# mainboard_rs485_v1_3.net
KiCad netlist of a schematic drawn in Altium Designer
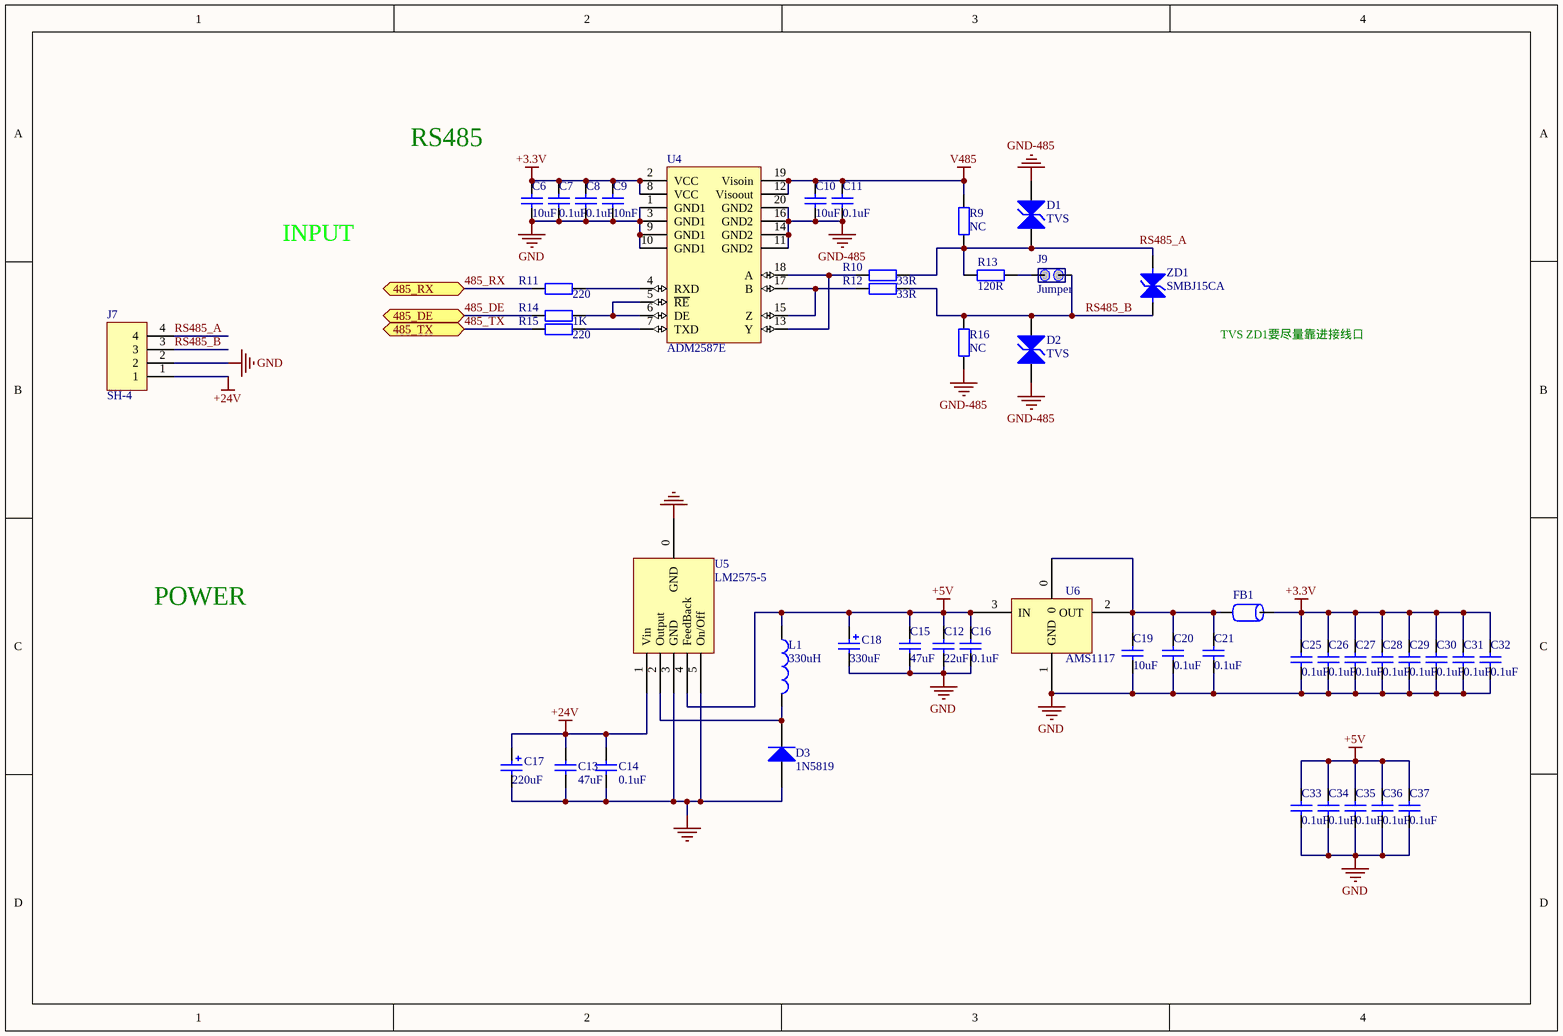
[diagram p0: mainboard_rs485.v1.3.SchDoc]

(export (version "E")
  (design (tool "Eeschema 10.0.6"))
  (components
    (comp (ref "C6")
      (value "10uF")
      (footprint "0805")
      (description "Capacitor")
      (fields (field (name "PUBLISHER") "Altium Limited"))
      (libsource (lib "TIAN's Schlib") (part "Cap"))
    )
    (comp (ref "C7")
      (value "0.1uF")
      (footprint "0805")
      (description "Capacitor")
      (fields (field (name "PUBLISHER") "Altium Limited"))
      (libsource (lib "TIAN's Schlib") (part "Cap"))
    )
    (comp (ref "C8")
      (value "0.1uF")
      (footprint "0805")
      (description "Capacitor")
      (fields (field (name "PUBLISHER") "Altium Limited"))
      (libsource (lib "TIAN's Schlib") (part "Cap"))
    )
    (comp (ref "C9")
      (value "10nF")
      (footprint "0805")
      (description "Capacitor")
      (fields (field (name "PUBLISHER") "Altium Limited"))
      (libsource (lib "TIAN's Schlib") (part "Cap"))
    )
    (comp (ref "C10")
      (value "10uF")
      (footprint "0805")
      (description "Capacitor")
      (fields (field (name "PUBLISHER") "Altium Limited"))
      (libsource (lib "TIAN's Schlib") (part "Cap"))
    )
    (comp (ref "C11")
      (value "0.1uF")
      (footprint "0805")
      (description "Capacitor")
      (fields (field (name "PUBLISHER") "Altium Limited"))
      (libsource (lib "TIAN's Schlib") (part "Cap"))
    )
    (comp (ref "C12") (value "22uF") (footprint "1206") (libsource (lib "Componet") (part "Cap0805")))
    (comp (ref "C13")
      (value "47uF")
      (footprint "1812")
      (description "Capacitor")
      (fields (field (name "PUBLISHER") "Altium Limited"))
      (libsource (lib "Miscellaneous Devices") (part "Cap"))
    )
    (comp (ref "C14")
      (value "0.1uF")
      (footprint "0805")
      (description "Capacitor")
      (fields (field (name "PUBLISHER") "Altium Limited"))
      (libsource (lib "Miscellaneous Devices") (part "Cap"))
    )
    (comp (ref "C15") (value "47uF") (footprint "1812") (libsource (lib "Componet") (part "Cap0805")))
    (comp (ref "C16") (value "0.1uF") (footprint "0805") (libsource (lib "Componet") (part "Cap0805")))
    (comp (ref "C17")
      (value "220uF")
      (footprint "CAP-5mm")
      (description "Polarized Capacitor (Radial)")
      (fields (field (name "PUBLISHER") "Altium Limited"))
      (libsource (lib "Miscellaneous Devices") (part "Cap Pol1"))
    )
    (comp (ref "C18")
      (value "330uF")
      (footprint "CAP-5mm")
      (description "Polarized Capacitor (Radial)")
      (fields (field (name "PUBLISHER") "Altium Limited"))
      (libsource (lib "Miscellaneous Devices") (part "Cap Pol1"))
    )
    (comp (ref "C19") (value "10uF") (footprint "0805") (libsource (lib "Componet") (part "Cap0805")))
    (comp (ref "C20") (value "0.1uF") (footprint "0805") (libsource (lib "Componet") (part "Cap0805")))
    (comp (ref "C21") (value "0.1uF") (footprint "0805") (libsource (lib "Componet") (part "Cap0805")))
    (comp (ref "C25") (value "0.1uF") (footprint "0805") (libsource (lib "Componet") (part "Cap0805")))
    (comp (ref "C26") (value "0.1uF") (footprint "0805") (libsource (lib "Componet") (part "Cap0805")))
    (comp (ref "C27") (value "0.1uF") (footprint "0805") (libsource (lib "Componet") (part "Cap0805")))
    (comp (ref "C28") (value "0.1uF") (footprint "0805") (libsource (lib "Componet") (part "Cap0805")))
    (comp (ref "C29") (value "0.1uF") (footprint "0805") (libsource (lib "Componet") (part "Cap0805")))
    (comp (ref "C30") (value "0.1uF") (footprint "0805") (libsource (lib "Componet") (part "Cap0805")))
    (comp (ref "C31") (value "0.1uF") (footprint "0805") (libsource (lib "Componet") (part "Cap0805")))
    (comp (ref "C32") (value "0.1uF") (footprint "0805") (libsource (lib "Componet") (part "Cap0805")))
    (comp (ref "C33") (value "0.1uF") (footprint "0805") (libsource (lib "Componet") (part "Cap0805")))
    (comp (ref "C34") (value "0.1uF") (footprint "0805") (libsource (lib "Componet") (part "Cap0805")))
    (comp (ref "C35") (value "0.1uF") (footprint "0805") (libsource (lib "Componet") (part "Cap0805")))
    (comp (ref "C36") (value "0.1uF") (footprint "0805") (libsource (lib "Componet") (part "Cap0805")))
    (comp (ref "C37") (value "0.1uF") (footprint "0805") (libsource (lib "Componet") (part "Cap0805")))
    (comp (ref "D1")
      (value "TVS")
      (footprint "SMBJ_DO-214")
      (fields (field (name "PUBLISHER") "Altium Limited"))
      (libsource (lib "TIAN's Schlib") (part "TVS"))
    )
    (comp (ref "D2")
      (value "TVS")
      (footprint "SMBJ_DO-214")
      (fields (field (name "PUBLISHER") "Altium Limited"))
      (libsource (lib "TIAN's Schlib") (part "TVS"))
    )
    (comp (ref "D3")
      (value "1N5819")
      (footprint "Diode_TP2")
      (description "High Conductance Fast Diode")
      (fields (field (name "PUBLISHER") "Altium Limited"))
      (libsource (lib "Miscellaneous Devices") (part "Diode 1N4148"))
    )
    (comp (ref "FB1") (value "FERRITE") (footprint "0805") (libsource (lib "Connector") (part "FERRITE")))
    (comp (ref "J7") (value "SH-4") (footprint "PWR") (libsource (lib "Connector") (part "SH-4")))
    (comp (ref "J9") (value "Jumper") (footprint "J254-2") (libsource (lib "Connector") (part "Jumper")))
    (comp (ref "L1")
      (value "330uH")
      (footprint "Inductance")
      (description "Inductor")
      (fields (field (name "PUBLISHER") "Altium Limited"))
      (libsource (lib "Miscellaneous Devices") (part "Inductor"))
    )
    (comp (ref "R9")
      (value "NC")
      (footprint "0805")
      (description "Resistor")
      (fields (field (name "PUBLISHER") "Altium Limited"))
      (libsource (lib "") (part "Res2_1"))
    )
    (comp (ref "R10")
      (value "33R")
      (footprint "0805")
      (description "Resistor")
      (fields (field (name "PUBLISHER") "Altium Limited"))
      (libsource (lib "TIAN's Schlib") (part "Res2"))
    )
    (comp (ref "R11")
      (value "220")
      (footprint "0805")
      (description "Resistor")
      (fields (field (name "PUBLISHER") "Altium Limited"))
      (libsource (lib "") (part "Res2_1"))
    )
    (comp (ref "R12")
      (value "33R")
      (footprint "0805")
      (description "Resistor")
      (fields (field (name "PUBLISHER") "Altium Limited"))
      (libsource (lib "TIAN's Schlib") (part "Res2"))
    )
    (comp (ref "R13")
      (value "120R")
      (footprint "0805")
      (description "Resistor")
      (fields (field (name "PUBLISHER") "Altium Limited"))
      (libsource (lib "") (part "Res2_2"))
    )
    (comp (ref "R14")
      (value "1K")
      (footprint "0805")
      (description "Resistor")
      (fields (field (name "PUBLISHER") "Altium Limited"))
      (libsource (lib "") (part "Res2_1"))
    )
    (comp (ref "R15")
      (value "220")
      (footprint "0805")
      (description "Resistor")
      (fields (field (name "PUBLISHER") "Altium Limited"))
      (libsource (lib "") (part "Res2_1"))
    )
    (comp (ref "R16")
      (value "NC")
      (footprint "0805")
      (description "Resistor")
      (fields (field (name "PUBLISHER") "Altium Limited"))
      (libsource (lib "") (part "Res2_1"))
    )
    (comp (ref "U4")
      (value "ADM2587E")
      (footprint "SOIC_W_20")
      (description "isolated DC-DC RS485")
      (libsource (lib "TIAN's Schlib") (part "ADM2587E"))
    )
    (comp (ref "U5") (value "LM2575-5") (footprint "TO-263") (libsource (lib "Leon") (part "LM25XX")))
    (comp (ref "U6") (value "AMS1117") (footprint "TO-223") (libsource (lib "Chip") (part "AMS1117")))
    (comp (ref "ZD1")
      (value "SMBJ15CA")
      (footprint "DO-214AA/SMB")
      (description "瞬态抑制二极管")
      (libsource (lib "ALARM") (part "TVS"))
    )
  )
  (nets
    (net (code "1") (name "+3.3V") (class "Default")
      (node (ref "C25") (pin "2") (pinfunction "2_2") (pintype "passive"))
      (node (ref "C26") (pin "2") (pinfunction "2_2") (pintype "passive"))
      (node (ref "C27") (pin "2") (pinfunction "2_2") (pintype "passive"))
      (node (ref "C28") (pin "2") (pinfunction "2_2") (pintype "passive"))
      (node (ref "C29") (pin "2") (pinfunction "2_2") (pintype "passive"))
      (node (ref "C30") (pin "2") (pinfunction "2_2") (pintype "passive"))
      (node (ref "C31") (pin "2") (pinfunction "2_2") (pintype "passive"))
      (node (ref "C32") (pin "2") (pinfunction "2_2") (pintype "passive"))
      (node (ref "C6") (pin "2") (pinfunction "2_2") (pintype "passive"))
      (node (ref "C7") (pin "2") (pinfunction "2_2") (pintype "passive"))
      (node (ref "C8") (pin "2") (pinfunction "2_2") (pintype "passive"))
      (node (ref "C9") (pin "2") (pinfunction "2_2") (pintype "passive"))
      (node (ref "FB1") (pin "2") (pinfunction "2_2") (pintype "passive"))
      (node (ref "U4") (pin "2") (pinfunction "VCC_2") (pintype "passive"))
      (node (ref "U4") (pin "8") (pinfunction "VCC_8") (pintype "passive"))
    )
    (net (code "2") (name "+5V") (class "Default")
      (node (ref "C12") (pin "2") (pinfunction "2_2") (pintype "passive"))
      (node (ref "C15") (pin "2") (pinfunction "2_2") (pintype "passive"))
      (node (ref "C16") (pin "2") (pinfunction "2_2") (pintype "passive"))
      (node (ref "C18") (pin "1") (pinfunction "1_1") (pintype "passive"))
      (node (ref "C33") (pin "2") (pinfunction "2_2") (pintype "passive"))
      (node (ref "C34") (pin "2") (pinfunction "2_2") (pintype "passive"))
      (node (ref "C35") (pin "2") (pinfunction "2_2") (pintype "passive"))
      (node (ref "C36") (pin "2") (pinfunction "2_2") (pintype "passive"))
      (node (ref "C37") (pin "2") (pinfunction "2_2") (pintype "passive"))
      (node (ref "L1") (pin "1") (pinfunction "1_1") (pintype "passive"))
      (node (ref "U5") (pin "4") (pinfunction "FeedBack_4") (pintype "passive"))
      (node (ref "U6") (pin "3") (pinfunction "IN_3") (pintype "passive"))
    )
    (net (code "3") (name "+24V") (class "Default")
      (node (ref "C13") (pin "2") (pinfunction "2_2") (pintype "passive"))
      (node (ref "C14") (pin "2") (pinfunction "2_2") (pintype "passive"))
      (node (ref "C17") (pin "1") (pinfunction "1_1") (pintype "passive"))
      (node (ref "J7") (pin "1") (pinfunction "1_1") (pintype "passive"))
      (node (ref "U5") (pin "1") (pinfunction "Vin_1") (pintype "passive"))
    )
    (net (code "4") (name "/485_DE") (class "Default")
      (node (ref "R14") (pin "1") (pinfunction "1_1") (pintype "passive"))
    )
    (net (code "5") (name "/485_RX") (class "Default")
      (node (ref "R11") (pin "1") (pinfunction "1_1") (pintype "passive"))
    )
    (net (code "6") (name "/485_TX") (class "Default")
      (node (ref "R15") (pin "1") (pinfunction "1_1") (pintype "passive"))
    )
    (net (code "7") (name "/RS485_A") (class "Default")
      (node (ref "D1") (pin "2") (pinfunction "K_2") (pintype "passive"))
      (node (ref "J7") (pin "4") (pinfunction "4_4") (pintype "passive"))
      (node (ref "R10") (pin "2") (pinfunction "2_2") (pintype "passive"))
      (node (ref "R13") (pin "2") (pinfunction "2_2") (pintype "passive"))
      (node (ref "R9") (pin "1") (pinfunction "1_1") (pintype "passive"))
      (node (ref "ZD1") (pin "1") (pinfunction "1_1") (pintype "passive"))
    )
    (net (code "8") (name "/RS485_B") (class "Default")
      (node (ref "D2") (pin "2") (pinfunction "K_2") (pintype "passive"))
      (node (ref "J7") (pin "3") (pinfunction "3_3") (pintype "passive"))
      (node (ref "J9") (pin "1") (pinfunction "1_1") (pintype "passive"))
      (node (ref "R12") (pin "2") (pinfunction "2_2") (pintype "passive"))
      (node (ref "R16") (pin "2") (pinfunction "2_2") (pintype "passive"))
      (node (ref "ZD1") (pin "2") (pinfunction "2_2") (pintype "passive"))
    )
    (net (code "9") (name "GND") (class "Default")
      (node (ref "C12") (pin "1") (pinfunction "1_1") (pintype "passive"))
      (node (ref "C13") (pin "1") (pinfunction "1_1") (pintype "passive"))
      (node (ref "C14") (pin "1") (pinfunction "1_1") (pintype "passive"))
      (node (ref "C15") (pin "1") (pinfunction "1_1") (pintype "passive"))
      (node (ref "C16") (pin "1") (pinfunction "1_1") (pintype "passive"))
      (node (ref "C17") (pin "2") (pinfunction "2_2") (pintype "passive"))
      (node (ref "C18") (pin "2") (pinfunction "2_2") (pintype "passive"))
      (node (ref "C19") (pin "1") (pinfunction "1_1") (pintype "passive"))
      (node (ref "C20") (pin "1") (pinfunction "1_1") (pintype "passive"))
      (node (ref "C21") (pin "1") (pinfunction "1_1") (pintype "passive"))
      (node (ref "C25") (pin "1") (pinfunction "1_1") (pintype "passive"))
      (node (ref "C26") (pin "1") (pinfunction "1_1") (pintype "passive"))
      (node (ref "C27") (pin "1") (pinfunction "1_1") (pintype "passive"))
      (node (ref "C28") (pin "1") (pinfunction "1_1") (pintype "passive"))
      (node (ref "C29") (pin "1") (pinfunction "1_1") (pintype "passive"))
      (node (ref "C30") (pin "1") (pinfunction "1_1") (pintype "passive"))
      (node (ref "C31") (pin "1") (pinfunction "1_1") (pintype "passive"))
      (node (ref "C32") (pin "1") (pinfunction "1_1") (pintype "passive"))
      (node (ref "C33") (pin "1") (pinfunction "1_1") (pintype "passive"))
      (node (ref "C34") (pin "1") (pinfunction "1_1") (pintype "passive"))
      (node (ref "C35") (pin "1") (pinfunction "1_1") (pintype "passive"))
      (node (ref "C36") (pin "1") (pinfunction "1_1") (pintype "passive"))
      (node (ref "C37") (pin "1") (pinfunction "1_1") (pintype "passive"))
      (node (ref "C6") (pin "1") (pinfunction "1_1") (pintype "passive"))
      (node (ref "C7") (pin "1") (pinfunction "1_1") (pintype "passive"))
      (node (ref "C8") (pin "1") (pinfunction "1_1") (pintype "passive"))
      (node (ref "C9") (pin "1") (pinfunction "1_1") (pintype "passive"))
      (node (ref "D3") (pin "1") (pinfunction "A_1") (pintype "passive"))
      (node (ref "J7") (pin "2") (pinfunction "2_2") (pintype "passive"))
      (node (ref "U4") (pin "1") (pinfunction "GND1_1") (pintype "passive"))
      (node (ref "U4") (pin "10") (pinfunction "GND1_10") (pintype "passive"))
      (node (ref "U4") (pin "3") (pinfunction "GND1_3") (pintype "passive"))
      (node (ref "U4") (pin "9") (pinfunction "GND1_9") (pintype "passive"))
      (node (ref "U5") (pin "0") (pinfunction "GND_0") (pintype "passive"))
      (node (ref "U5") (pin "3") (pinfunction "GND_3") (pintype "passive"))
      (node (ref "U5") (pin "5") (pinfunction "On/Off_5") (pintype "passive"))
      (node (ref "U6") (pin "1") (pinfunction "GND_1") (pintype "passive"))
    )
    (net (code "10") (name "GND-485") (class "Default")
      (node (ref "C10") (pin "1") (pinfunction "1_1") (pintype "passive"))
      (node (ref "C11") (pin "1") (pinfunction "1_1") (pintype "passive"))
      (node (ref "D1") (pin "1") (pinfunction "A_1") (pintype "passive"))
      (node (ref "D2") (pin "1") (pinfunction "A_1") (pintype "passive"))
      (node (ref "R16") (pin "1") (pinfunction "1_1") (pintype "passive"))
      (node (ref "U4") (pin "11") (pinfunction "GND2_11") (pintype "passive"))
      (node (ref "U4") (pin "14") (pinfunction "GND2_14") (pintype "passive"))
      (node (ref "U4") (pin "16") (pinfunction "GND2_16") (pintype "passive"))
      (node (ref "U4") (pin "20") (pinfunction "GND2_20") (pintype "passive"))
    )
    (net (code "11") (name "Net-(D3-K)") (class "Default")
      (node (ref "D3") (pin "2") (pinfunction "K_2") (pintype "passive"))
      (node (ref "L1") (pin "2") (pinfunction "2_2") (pintype "passive"))
      (node (ref "U5") (pin "2") (pinfunction "Output_2") (pintype "passive"))
    )
    (net (code "12") (name "Net-(J9-Pad2)") (class "Default")
      (node (ref "J9") (pin "2") (pinfunction "2_2") (pintype "passive"))
      (node (ref "R13") (pin "1") (pinfunction "1_1") (pintype "passive"))
    )
    (net (code "13") (name "Net-(U4-A)") (class "Default")
      (node (ref "R10") (pin "1") (pinfunction "1_1") (pintype "passive"))
      (node (ref "U4") (pin "13") (pinfunction "Y_13") (pintype "bidirectional"))
      (node (ref "U4") (pin "18") (pinfunction "A_18") (pintype "bidirectional"))
    )
    (net (code "14") (name "Net-(U4-B)") (class "Default")
      (node (ref "R12") (pin "1") (pinfunction "1_1") (pintype "passive"))
      (node (ref "U4") (pin "15") (pinfunction "Z_15") (pintype "bidirectional"))
      (node (ref "U4") (pin "17") (pinfunction "B_17") (pintype "bidirectional"))
    )
    (net (code "15") (name "Net-(U4-DE)") (class "Default")
      (node (ref "R14") (pin "2") (pinfunction "2_2") (pintype "passive"))
      (node (ref "U4") (pin "5") (pinfunction "~{RE}_5") (pintype "bidirectional"))
      (node (ref "U4") (pin "6") (pinfunction "DE_6") (pintype "bidirectional"))
    )
    (net (code "16") (name "Net-(U4-RXD)") (class "Default")
      (node (ref "R11") (pin "2") (pinfunction "2_2") (pintype "passive"))
      (node (ref "U4") (pin "4") (pinfunction "RXD_4") (pintype "bidirectional"))
    )
    (net (code "17") (name "Net-(U4-TXD)") (class "Default")
      (node (ref "R15") (pin "2") (pinfunction "2_2") (pintype "passive"))
      (node (ref "U4") (pin "7") (pinfunction "TXD_7") (pintype "bidirectional"))
    )
    (net (code "18") (name "Net-(U6-OUT)") (class "Default")
      (node (ref "C19") (pin "2") (pinfunction "2_2") (pintype "passive"))
      (node (ref "C20") (pin "2") (pinfunction "2_2") (pintype "passive"))
      (node (ref "C21") (pin "2") (pinfunction "2_2") (pintype "passive"))
      (node (ref "FB1") (pin "1") (pinfunction "1_1") (pintype "passive"))
      (node (ref "U6") (pin "0") (pinfunction "0_0") (pintype "passive"))
      (node (ref "U6") (pin "2") (pinfunction "OUT_2") (pintype "passive"))
    )
    (net (code "19") (name "V485") (class "Default")
      (node (ref "C10") (pin "2") (pinfunction "2_2") (pintype "passive"))
      (node (ref "C11") (pin "2") (pinfunction "2_2") (pintype "passive"))
      (node (ref "R9") (pin "2") (pinfunction "2_2") (pintype "passive"))
      (node (ref "U4") (pin "12") (pinfunction "Visoout_12") (pintype "passive"))
      (node (ref "U4") (pin "19") (pinfunction "Visoin_19") (pintype "passive"))
    )
  )
)
